# RFM96W-BB.net
KiCad netlist of a schematic drawn in EAGLE
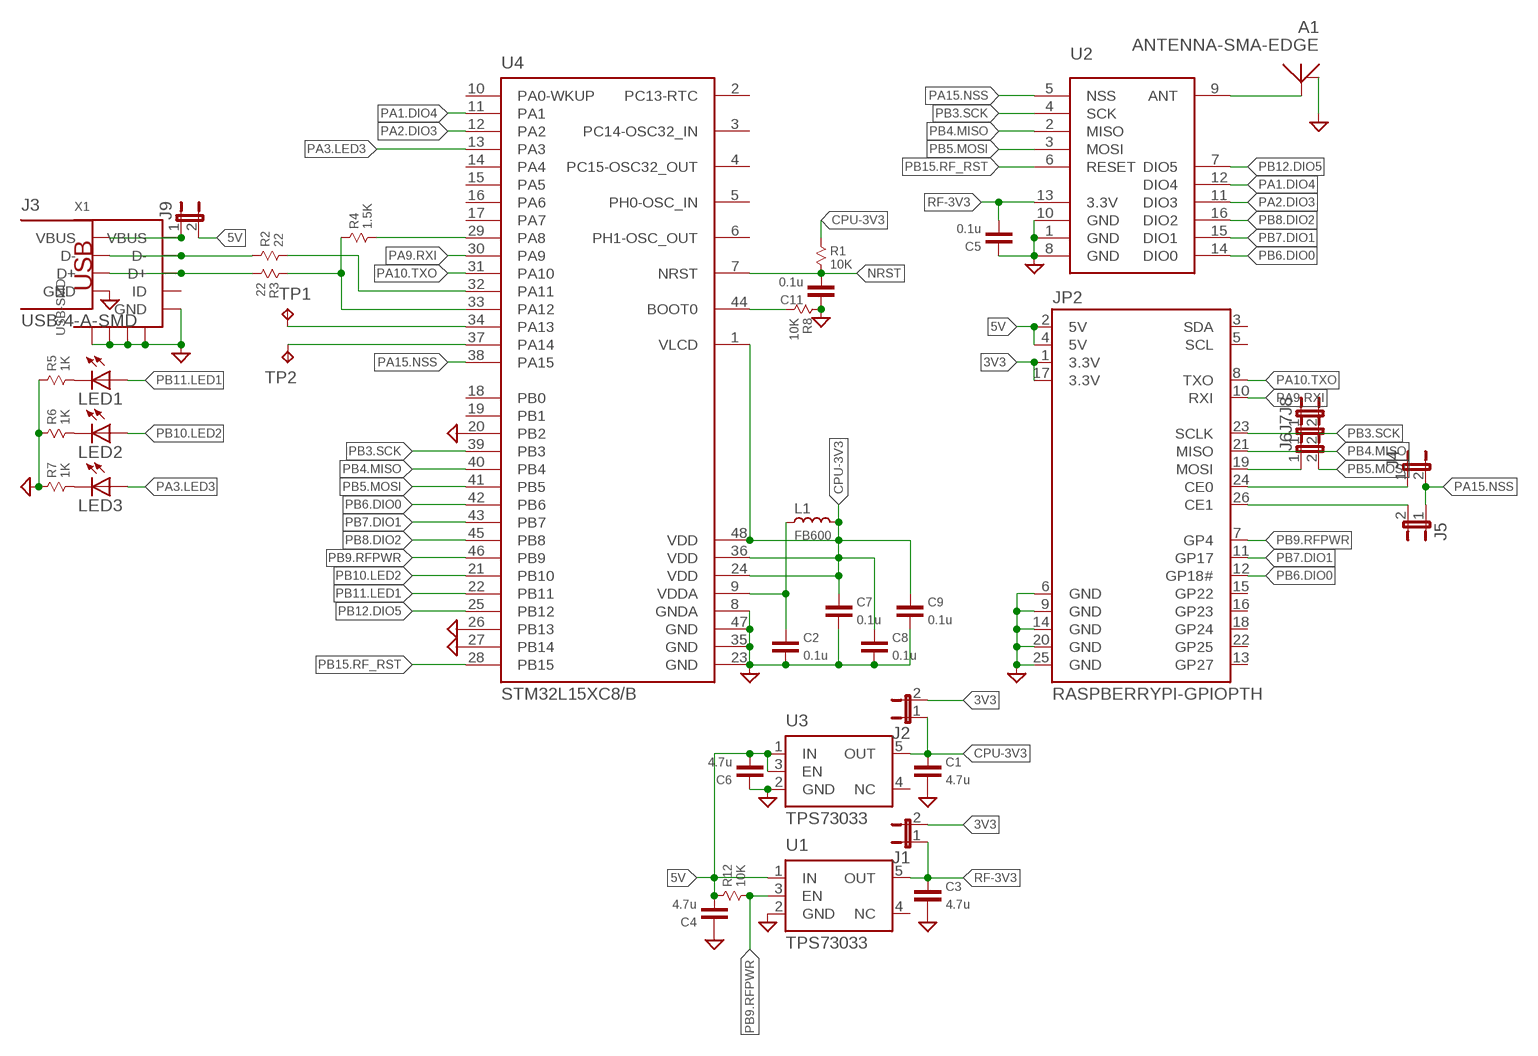
[diagram p0: schematic, sheet 1]

(export (version "E")
  (design (tool "Eeschema 10.0.6"))
  (components
    (comp (ref "A1")
      (value "ANTENNA-SMA-EDGE")
      (footprint "eagle-import:SMA-EDGE")
      (libsource (lib "eagle-import") (part "ANTENNA-SMA-EDGE"))
    )
    (comp (ref "C1")
      (value "4.7u")
      (footprint "eagle-import:0603")
      (libsource (lib "eagle-import") (part "CAP-0603"))
    )
    (comp (ref "C2")
      (value "0.1u")
      (footprint "eagle-import:0603")
      (libsource (lib "eagle-import") (part "CAP-0603"))
    )
    (comp (ref "C3")
      (value "4.7u")
      (footprint "eagle-import:0603")
      (libsource (lib "eagle-import") (part "CAP-0603"))
    )
    (comp (ref "C4")
      (value "4.7u")
      (footprint "eagle-import:0603")
      (libsource (lib "eagle-import") (part "CAP-0603"))
    )
    (comp (ref "C5")
      (value "0.1u")
      (footprint "eagle-import:0603")
      (libsource (lib "eagle-import") (part "CAP-0603"))
    )
    (comp (ref "C6")
      (value "4.7u")
      (footprint "eagle-import:0603")
      (libsource (lib "eagle-import") (part "CAP-0603"))
    )
    (comp (ref "C7")
      (value "0.1u")
      (footprint "eagle-import:0603")
      (libsource (lib "eagle-import") (part "CAP-0603"))
    )
    (comp (ref "C8")
      (value "0.1u")
      (footprint "eagle-import:0603")
      (libsource (lib "eagle-import") (part "CAP-0603"))
    )
    (comp (ref "C9")
      (value "0.1u")
      (footprint "eagle-import:0603")
      (libsource (lib "eagle-import") (part "CAP-0603"))
    )
    (comp (ref "C11")
      (value "0.1u")
      (footprint "eagle-import:0603")
      (libsource (lib "eagle-import") (part "CAP-0603"))
    )
    (comp (ref "J1")
      (value "JUMPER-2SMD-NO")
      (footprint "eagle-import:SJ_2S-NO")
      (libsource (lib "eagle-import") (part "JUMPER-2SMD-NO"))
    )
    (comp (ref "J2")
      (value "JUMPER-2SMD-NO")
      (footprint "eagle-import:SJ_2S-NO")
      (libsource (lib "eagle-import") (part "JUMPER-2SMD-NO"))
    )
    (comp (ref "J3")
      (value "USB-4-A-SMD")
      (footprint "eagle-import:USB-A-SMD")
      (libsource (lib "eagle-import") (part "USB-4-A-SMD"))
    )
    (comp (ref "J4")
      (value "JUMPER-2SMD-NO")
      (footprint "eagle-import:SJ_2S-NO")
      (libsource (lib "eagle-import") (part "JUMPER-2SMD-NO"))
    )
    (comp (ref "J5")
      (value "JUMPER-2SMD-NO")
      (footprint "eagle-import:SJ_2S-NO")
      (libsource (lib "eagle-import") (part "JUMPER-2SMD-NO"))
    )
    (comp (ref "J6")
      (value "JUMPER-2SMD-NO")
      (footprint "eagle-import:SJ_2S-NO")
      (libsource (lib "eagle-import") (part "JUMPER-2SMD-NO"))
    )
    (comp (ref "J7")
      (value "JUMPER-2SMD-NO")
      (footprint "eagle-import:SJ_2S-NO")
      (libsource (lib "eagle-import") (part "JUMPER-2SMD-NO"))
    )
    (comp (ref "J8")
      (value "JUMPER-2SMD-NO")
      (footprint "eagle-import:SJ_2S-NO")
      (libsource (lib "eagle-import") (part "JUMPER-2SMD-NO"))
    )
    (comp (ref "J9")
      (value "JUMPER-2SMD-NO")
      (footprint "eagle-import:SJ_2S-NO")
      (libsource (lib "eagle-import") (part "JUMPER-2SMD-NO"))
    )
    (comp (ref "JP2")
      (value "RASPBERRYPI-GPIOPTH")
      (footprint "eagle-import:2X13-SHROUDED")
      (libsource (lib "eagle-import") (part "RASPBERRYPI-GPIOPTH"))
    )
    (comp (ref "L1")
      (value "FB600")
      (footprint "eagle-import:0603")
      (libsource (lib "eagle-import") (part "INDUCTOR-0603"))
    )
    (comp (ref "LED1")
      (value "LEDCHIPLED_0603")
      (footprint "eagle-import:CHIPLED_0603")
      (libsource (lib "eagle-import") (part "LEDCHIPLED_0603"))
    )
    (comp (ref "LED2")
      (value "LEDCHIPLED_0603")
      (footprint "eagle-import:CHIPLED_0603")
      (libsource (lib "eagle-import") (part "LEDCHIPLED_0603"))
    )
    (comp (ref "LED3")
      (value "LEDCHIPLED_0603")
      (footprint "eagle-import:CHIPLED_0603")
      (libsource (lib "eagle-import") (part "LEDCHIPLED_0603"))
    )
    (comp (ref "R1")
      (value "10K")
      (footprint "eagle-import:0603")
      (libsource (lib "eagle-import") (part "RESISTOR-0603"))
    )
    (comp (ref "R2")
      (value "22")
      (footprint "eagle-import:0603")
      (libsource (lib "eagle-import") (part "RESISTOR-0603"))
    )
    (comp (ref "R3")
      (value "22")
      (footprint "eagle-import:0603")
      (libsource (lib "eagle-import") (part "RESISTOR-0603"))
    )
    (comp (ref "R4")
      (value "1.5K")
      (footprint "eagle-import:0603")
      (libsource (lib "eagle-import") (part "RESISTOR-0603"))
    )
    (comp (ref "R5")
      (value "1K")
      (footprint "eagle-import:0603")
      (libsource (lib "eagle-import") (part "RESISTOR-0603"))
    )
    (comp (ref "R6")
      (value "1K")
      (footprint "eagle-import:0603")
      (libsource (lib "eagle-import") (part "RESISTOR-0603"))
    )
    (comp (ref "R7")
      (value "1K")
      (footprint "eagle-import:0603")
      (libsource (lib "eagle-import") (part "RESISTOR-0603"))
    )
    (comp (ref "R8")
      (value "10K")
      (footprint "eagle-import:0603")
      (libsource (lib "eagle-import") (part "RESISTOR-0603"))
    )
    (comp (ref "R12")
      (value "10K")
      (footprint "eagle-import:0603")
      (libsource (lib "eagle-import") (part "RESISTOR-0603"))
    )
    (comp (ref "TP1")
      (value "TPTP14R")
      (footprint "eagle-import:TP14R")
      (libsource (lib "eagle-import") (part "TPTP14R"))
    )
    (comp (ref "TP2")
      (value "TPTP14R")
      (footprint "eagle-import:TP14R")
      (libsource (lib "eagle-import") (part "TPTP14R"))
    )
    (comp (ref "U1")
      (value "TPS73033")
      (footprint "eagle-import:SOT23-5")
      (libsource (lib "eagle-import") (part "TPS73033"))
    )
    (comp (ref "U2")
      (value "RFM9XW")
      (footprint "eagle-import:RFM9XW")
      (libsource (lib "eagle-import") (part "RFM9XW"))
    )
    (comp (ref "U3")
      (value "TPS73033")
      (footprint "eagle-import:SOT23-5")
      (libsource (lib "eagle-import") (part "TPS73033"))
    )
    (comp (ref "U4")
      (value "STM32L15XC8/B")
      (footprint "eagle-import:LQFP48")
      (libsource (lib "eagle-import") (part "STM32L15XC8/B"))
    )
    (comp (ref "X1")
      (value "USB-SMD")
      (footprint "eagle-import:USB-MINIB")
      (libsource (lib "eagle-import") (part "USB-SMD"))
    )
  )
  (nets
    (net (code "1") (name "3V3") (class "Default")
      (node (ref "J1") (pin "2") (pinfunction "2_2") (pintype "passive"))
      (node (ref "J2") (pin "2") (pinfunction "2_2") (pintype "passive"))
      (node (ref "JP2") (pin "1") (pinfunction "3.3V_1") (pintype "power_in"))
      (node (ref "JP2") (pin "17") (pinfunction "3.3V_17") (pintype "power_in"))
    )
    (net (code "2") (name "5V") (class "Default")
      (node (ref "C4") (pin "1") (pinfunction "1_1") (pintype "passive"))
      (node (ref "C6") (pin "1") (pinfunction "1_1") (pintype "passive"))
      (node (ref "J9") (pin "2") (pinfunction "2_2") (pintype "passive"))
      (node (ref "JP2") (pin "2") (pinfunction "5V_2") (pintype "power_in"))
      (node (ref "JP2") (pin "4") (pinfunction "5V_4") (pintype "power_in"))
      (node (ref "R12") (pin "1") (pinfunction "1_1") (pintype "passive"))
      (node (ref "U1") (pin "1") (pinfunction "IN_1") (pintype "passive"))
      (node (ref "U3") (pin "1") (pinfunction "IN_1") (pintype "passive"))
      (node (ref "U3") (pin "3") (pinfunction "EN_3") (pintype "input"))
    )
    (net (code "3") (name "CPU-3V3") (class "Default")
      (node (ref "C1") (pin "2") (pinfunction "2_2") (pintype "passive"))
      (node (ref "C7") (pin "2") (pinfunction "2_2") (pintype "passive"))
      (node (ref "C8") (pin "2") (pinfunction "2_2") (pintype "passive"))
      (node (ref "C9") (pin "2") (pinfunction "2_2") (pintype "passive"))
      (node (ref "J2") (pin "1") (pinfunction "1_1") (pintype "passive"))
      (node (ref "L1") (pin "2") (pinfunction "2_2") (pintype "passive"))
      (node (ref "R1") (pin "1") (pinfunction "1_1") (pintype "passive"))
      (node (ref "U3") (pin "5") (pinfunction "OUT_5") (pintype "passive"))
      (node (ref "U4") (pin "1") (pinfunction "VLCD_1") (pintype "passive"))
      (node (ref "U4") (pin "24") (pinfunction "VDD_24") (pintype "power_in"))
      (node (ref "U4") (pin "36") (pinfunction "VDD_36") (pintype "power_in"))
      (node (ref "U4") (pin "48") (pinfunction "VDD_48") (pintype "power_in"))
    )
    (net (code "4") (name "GND") (class "Default")
      (node (ref "A1") (pin "GND@1") (pinfunction "GND_GND@1") (pintype "power_in"))
      (node (ref "C1") (pin "1") (pinfunction "1_1") (pintype "passive"))
      (node (ref "C11") (pin "2") (pinfunction "2_2") (pintype "passive"))
      (node (ref "C2") (pin "1") (pinfunction "1_1") (pintype "passive"))
      (node (ref "C3") (pin "1") (pinfunction "1_1") (pintype "passive"))
      (node (ref "C4") (pin "2") (pinfunction "2_2") (pintype "passive"))
      (node (ref "C5") (pin "2") (pinfunction "2_2") (pintype "passive"))
      (node (ref "C6") (pin "2") (pinfunction "2_2") (pintype "passive"))
      (node (ref "C7") (pin "1") (pinfunction "1_1") (pintype "passive"))
      (node (ref "C8") (pin "1") (pinfunction "1_1") (pintype "passive"))
      (node (ref "C9") (pin "1") (pinfunction "1_1") (pintype "passive"))
      (node (ref "J3") (pin "GND") (pinfunction "GND_GND") (pintype "power_in"))
      (node (ref "JP2") (pin "14") (pinfunction "GND_14") (pintype "power_in"))
      (node (ref "JP2") (pin "20") (pinfunction "GND_20") (pintype "power_in"))
      (node (ref "JP2") (pin "25") (pinfunction "GND_25") (pintype "power_in"))
      (node (ref "JP2") (pin "6") (pinfunction "GND_6") (pintype "power_in"))
      (node (ref "JP2") (pin "9") (pinfunction "GND_9") (pintype "power_in"))
      (node (ref "R5") (pin "1") (pinfunction "1_1") (pintype "passive"))
      (node (ref "R6") (pin "1") (pinfunction "1_1") (pintype "passive"))
      (node (ref "R7") (pin "1") (pinfunction "1_1") (pintype "passive"))
      (node (ref "R8") (pin "1") (pinfunction "1_1") (pintype "passive"))
      (node (ref "U1") (pin "2") (pinfunction "GND_2") (pintype "power_in"))
      (node (ref "U2") (pin "1") (pinfunction "GND_1") (pintype "power_in"))
      (node (ref "U2") (pin "10") (pinfunction "GND_10") (pintype "power_in"))
      (node (ref "U2") (pin "8") (pinfunction "GND_8") (pintype "power_in"))
      (node (ref "U3") (pin "2") (pinfunction "GND_2") (pintype "power_in"))
      (node (ref "U4") (pin "20") (pinfunction "PB2_20") (pintype "bidirectional"))
      (node (ref "U4") (pin "23") (pinfunction "GND_23") (pintype "power_in"))
      (node (ref "U4") (pin "26") (pinfunction "PB13_26") (pintype "bidirectional"))
      (node (ref "U4") (pin "27") (pinfunction "PB14_27") (pintype "bidirectional"))
      (node (ref "U4") (pin "35") (pinfunction "GND_35") (pintype "power_in"))
      (node (ref "U4") (pin "47") (pinfunction "GND_47") (pintype "power_in"))
      (node (ref "U4") (pin "8") (pinfunction "GNDA_8") (pintype "power_in"))
      (node (ref "X1") (pin "GND") (pinfunction "GND_GND") (pintype "power_in"))
      (node (ref "X1") (pin "GND@1") (pinfunction "GND_GND@1") (pintype "power_in"))
      (node (ref "X1") (pin "GND@2") (pinfunction "GND_GND@2") (pintype "power_in"))
      (node (ref "X1") (pin "GND@3") (pinfunction "GND_GND@3") (pintype "power_in"))
      (node (ref "X1") (pin "GND@4") (pinfunction "GND_GND@4") (pintype "power_in"))
    )
    (net (code "5") (name "NRST") (class "Default")
      (node (ref "C11") (pin "1") (pinfunction "1_1") (pintype "passive"))
      (node (ref "R1") (pin "2") (pinfunction "2_2") (pintype "passive"))
      (node (ref "U4") (pin "7") (pinfunction "NRST_7") (pintype "input"))
    )
    (net (code "6") (name "Net-(J3-PadD+)") (class "Default")
      (node (ref "J3") (pin "D+") (pinfunction "D+_D+") (pintype "bidirectional"))
      (node (ref "R3") (pin "2") (pinfunction "2_2") (pintype "passive"))
      (node (ref "X1") (pin "D+") (pinfunction "D+_D+") (pintype "bidirectional"))
    )
    (net (code "7") (name "Net-(J3-PadD-)") (class "Default")
      (node (ref "J3") (pin "D-") (pinfunction "D-_D-") (pintype "bidirectional"))
      (node (ref "R2") (pin "1") (pinfunction "1_1") (pintype "passive"))
      (node (ref "X1") (pin "D-") (pinfunction "D-_D-") (pintype "bidirectional"))
    )
    (net (code "8") (name "Net-(J3-VBUS)") (class "Default")
      (node (ref "J3") (pin "VUSB") (pinfunction "VBUS_VUSB") (pintype "passive"))
      (node (ref "J9") (pin "1") (pinfunction "1_1") (pintype "passive"))
      (node (ref "X1") (pin "VBUS") (pinfunction "VBUS_VBUS") (pintype "passive"))
    )
    (net (code "9") (name "Net-(JP2-CE0)") (class "Default")
      (node (ref "J4") (pin "1") (pinfunction "1_1") (pintype "passive"))
      (node (ref "JP2") (pin "24") (pinfunction "CE0_24") (pintype "output"))
    )
    (net (code "10") (name "Net-(JP2-CE1)") (class "Default")
      (node (ref "J5") (pin "2") (pinfunction "2_2") (pintype "passive"))
      (node (ref "JP2") (pin "26") (pinfunction "CE1_26") (pintype "output"))
    )
    (net (code "11") (name "Net-(JP2-MISO)") (class "Default")
      (node (ref "J7") (pin "1") (pinfunction "1_1") (pintype "passive"))
      (node (ref "JP2") (pin "21") (pinfunction "MISO_21") (pintype "input"))
    )
    (net (code "12") (name "Net-(JP2-MOSI)") (class "Default")
      (node (ref "J6") (pin "1") (pinfunction "1_1") (pintype "passive"))
      (node (ref "JP2") (pin "19") (pinfunction "MOSI_19") (pintype "output"))
    )
    (net (code "13") (name "Net-(JP2-SCLK)") (class "Default")
      (node (ref "J8") (pin "1") (pinfunction "1_1") (pintype "passive"))
      (node (ref "JP2") (pin "23") (pinfunction "SCLK_23") (pintype "output"))
    )
    (net (code "14") (name "Net-(LED1-PadC)") (class "Default")
      (node (ref "LED1") (pin "C") (pinfunction "C_C") (pintype "passive"))
      (node (ref "R5") (pin "2") (pinfunction "2_2") (pintype "passive"))
    )
    (net (code "15") (name "Net-(LED2-PadC)") (class "Default")
      (node (ref "LED2") (pin "C") (pinfunction "C_C") (pintype "passive"))
      (node (ref "R6") (pin "2") (pinfunction "2_2") (pintype "passive"))
    )
    (net (code "16") (name "Net-(LED3-PadC)") (class "Default")
      (node (ref "LED3") (pin "C") (pinfunction "C_C") (pintype "passive"))
      (node (ref "R7") (pin "2") (pinfunction "2_2") (pintype "passive"))
    )
    (net (code "17") (name "Net-(U2-ANT)") (class "Default")
      (node (ref "A1") (pin "ANT") (pinfunction "ANT_ANT") (pintype "passive"))
      (node (ref "U2") (pin "9") (pinfunction "ANT_9") (pintype "passive"))
    )
    (net (code "18") (name "Net-(U4-BOOT0)") (class "Default")
      (node (ref "R8") (pin "2") (pinfunction "2_2") (pintype "passive"))
      (node (ref "U4") (pin "44") (pinfunction "BOOT0_44") (pintype "input"))
    )
    (net (code "19") (name "Net-(U4-PA8)") (class "Default")
      (node (ref "R4") (pin "2") (pinfunction "2_2") (pintype "passive"))
      (node (ref "U4") (pin "29") (pinfunction "PA8_29") (pintype "bidirectional"))
    )
    (net (code "20") (name "Net-(U4-PA11)") (class "Default")
      (node (ref "R2") (pin "2") (pinfunction "2_2") (pintype "passive"))
      (node (ref "U4") (pin "32") (pinfunction "PA11_32") (pintype "bidirectional"))
    )
    (net (code "21") (name "Net-(U4-PA12)") (class "Default")
      (node (ref "R3") (pin "1") (pinfunction "1_1") (pintype "passive"))
      (node (ref "R4") (pin "1") (pinfunction "1_1") (pintype "passive"))
      (node (ref "U4") (pin "33") (pinfunction "PA12_33") (pintype "bidirectional"))
    )
    (net (code "22") (name "Net-(U4-PA13)") (class "Default")
      (node (ref "TP1") (pin "TP") (pinfunction "TP_TP") (pintype "input"))
      (node (ref "U4") (pin "34") (pinfunction "PA13_34") (pintype "bidirectional"))
    )
    (net (code "23") (name "Net-(U4-PA14)") (class "Default")
      (node (ref "TP2") (pin "TP") (pinfunction "TP_TP") (pintype "input"))
      (node (ref "U4") (pin "37") (pinfunction "PA14_37") (pintype "bidirectional"))
    )
    (net (code "24") (name "Net-(U4-VDDA)") (class "Default")
      (node (ref "C2") (pin "2") (pinfunction "2_2") (pintype "passive"))
      (node (ref "L1") (pin "1") (pinfunction "1_1") (pintype "passive"))
      (node (ref "U4") (pin "9") (pinfunction "VDDA_9") (pintype "power_in"))
    )
    (net (code "25") (name "PA1.DIO4") (class "Default")
      (node (ref "U2") (pin "12") (pinfunction "DIO4_12") (pintype "bidirectional"))
      (node (ref "U4") (pin "11") (pinfunction "PA1_11") (pintype "bidirectional"))
    )
    (net (code "26") (name "PA2.DIO3") (class "Default")
      (node (ref "U2") (pin "11") (pinfunction "DIO3_11") (pintype "bidirectional"))
      (node (ref "U4") (pin "12") (pinfunction "PA2_12") (pintype "bidirectional"))
    )
    (net (code "27") (name "PA3.LED3") (class "Default")
      (node (ref "LED3") (pin "A") (pinfunction "A_A") (pintype "passive"))
      (node (ref "U4") (pin "13") (pinfunction "PA3_13") (pintype "bidirectional"))
    )
    (net (code "28") (name "PA9.RXI") (class "Default")
      (node (ref "JP2") (pin "10") (pinfunction "RXI_10") (pintype "input"))
      (node (ref "U4") (pin "30") (pinfunction "PA9_30") (pintype "bidirectional"))
    )
    (net (code "29") (name "PA10.TXO") (class "Default")
      (node (ref "JP2") (pin "8") (pinfunction "TXO_8") (pintype "output"))
      (node (ref "U4") (pin "31") (pinfunction "PA10_31") (pintype "bidirectional"))
    )
    (net (code "30") (name "PA15.NSS") (class "Default")
      (node (ref "J4") (pin "2") (pinfunction "2_2") (pintype "passive"))
      (node (ref "J5") (pin "1") (pinfunction "1_1") (pintype "passive"))
      (node (ref "U2") (pin "5") (pinfunction "NSS_5") (pintype "input"))
      (node (ref "U4") (pin "38") (pinfunction "PA15_38") (pintype "bidirectional"))
    )
    (net (code "31") (name "PB3.SCK") (class "Default")
      (node (ref "J8") (pin "2") (pinfunction "2_2") (pintype "passive"))
      (node (ref "U2") (pin "4") (pinfunction "SCK_4") (pintype "input"))
      (node (ref "U4") (pin "39") (pinfunction "PB3_39") (pintype "bidirectional"))
    )
    (net (code "32") (name "PB4.MISO") (class "Default")
      (node (ref "J7") (pin "2") (pinfunction "2_2") (pintype "passive"))
      (node (ref "U2") (pin "2") (pinfunction "MISO_2") (pintype "output"))
      (node (ref "U4") (pin "40") (pinfunction "PB4_40") (pintype "bidirectional"))
    )
    (net (code "33") (name "PB5.MOSI") (class "Default")
      (node (ref "J6") (pin "2") (pinfunction "2_2") (pintype "passive"))
      (node (ref "U2") (pin "3") (pinfunction "MOSI_3") (pintype "input"))
      (node (ref "U4") (pin "41") (pinfunction "PB5_41") (pintype "bidirectional"))
    )
    (net (code "34") (name "PB6.DIO0") (class "Default")
      (node (ref "JP2") (pin "12") (pinfunction "GP18#_12") (pintype "bidirectional"))
      (node (ref "U2") (pin "14") (pinfunction "DIO0_14") (pintype "bidirectional"))
      (node (ref "U4") (pin "42") (pinfunction "PB6_42") (pintype "bidirectional"))
    )
    (net (code "35") (name "PB7.DIO1") (class "Default")
      (node (ref "JP2") (pin "11") (pinfunction "GP17_11") (pintype "bidirectional"))
      (node (ref "U2") (pin "15") (pinfunction "DIO1_15") (pintype "bidirectional"))
      (node (ref "U4") (pin "43") (pinfunction "PB7_43") (pintype "bidirectional"))
    )
    (net (code "36") (name "PB8.DIO2") (class "Default")
      (node (ref "U2") (pin "16") (pinfunction "DIO2_16") (pintype "bidirectional"))
      (node (ref "U4") (pin "45") (pinfunction "PB8_45") (pintype "bidirectional"))
    )
    (net (code "37") (name "PB9.RFPWR") (class "Default")
      (node (ref "JP2") (pin "7") (pinfunction "GP4_7") (pintype "bidirectional"))
      (node (ref "R12") (pin "2") (pinfunction "2_2") (pintype "passive"))
      (node (ref "U1") (pin "3") (pinfunction "EN_3") (pintype "input"))
      (node (ref "U4") (pin "46") (pinfunction "PB9_46") (pintype "bidirectional"))
    )
    (net (code "38") (name "PB10.LED2") (class "Default")
      (node (ref "LED2") (pin "A") (pinfunction "A_A") (pintype "passive"))
      (node (ref "U4") (pin "21") (pinfunction "PB10_21") (pintype "bidirectional"))
    )
    (net (code "39") (name "PB11.LED1") (class "Default")
      (node (ref "LED1") (pin "A") (pinfunction "A_A") (pintype "passive"))
      (node (ref "U4") (pin "22") (pinfunction "PB11_22") (pintype "bidirectional"))
    )
    (net (code "40") (name "PB12.DIO5") (class "Default")
      (node (ref "U2") (pin "7") (pinfunction "DIO5_7") (pintype "bidirectional"))
      (node (ref "U4") (pin "25") (pinfunction "PB12_25") (pintype "bidirectional"))
    )
    (net (code "41") (name "PB15.RF_RST") (class "Default")
      (node (ref "U2") (pin "6") (pinfunction "RESET_6") (pintype "input"))
      (node (ref "U4") (pin "28") (pinfunction "PB15_28") (pintype "bidirectional"))
    )
    (net (code "42") (name "RF-3V3") (class "Default")
      (node (ref "C3") (pin "2") (pinfunction "2_2") (pintype "passive"))
      (node (ref "C5") (pin "1") (pinfunction "1_1") (pintype "passive"))
      (node (ref "J1") (pin "1") (pinfunction "1_1") (pintype "passive"))
      (node (ref "U1") (pin "5") (pinfunction "OUT_5") (pintype "passive"))
      (node (ref "U2") (pin "13") (pinfunction "3.3V_13") (pintype "power_in"))
    )
    (net (code "43") (name "unconnected-(JP2-GP22-Pad15)") (class "Default")
      (node (ref "JP2") (pin "15") (pinfunction "GP22_15") (pintype "bidirectional"))
    )
    (net (code "44") (name "unconnected-(JP2-GP23-Pad16)") (class "Default")
      (node (ref "JP2") (pin "16") (pinfunction "GP23_16") (pintype "bidirectional"))
    )
    (net (code "45") (name "unconnected-(JP2-GP24-Pad18)") (class "Default")
      (node (ref "JP2") (pin "18") (pinfunction "GP24_18") (pintype "bidirectional"))
    )
    (net (code "46") (name "unconnected-(JP2-GP25-Pad22)") (class "Default")
      (node (ref "JP2") (pin "22") (pinfunction "GP25_22") (pintype "bidirectional"))
    )
    (net (code "47") (name "unconnected-(JP2-GP27-Pad13)") (class "Default")
      (node (ref "JP2") (pin "13") (pinfunction "GP27_13") (pintype "bidirectional"))
    )
    (net (code "48") (name "unconnected-(JP2-SCL-Pad5)") (class "Default")
      (node (ref "JP2") (pin "5") (pinfunction "SCL_5") (pintype "bidirectional"))
    )
    (net (code "49") (name "unconnected-(JP2-SDA-Pad3)") (class "Default")
      (node (ref "JP2") (pin "3") (pinfunction "SDA_3") (pintype "bidirectional"))
    )
    (net (code "50") (name "unconnected-(U1-NC-Pad4)") (class "Default")
      (node (ref "U1") (pin "4") (pinfunction "NC_4") (pintype "no_connect"))
    )
    (net (code "51") (name "unconnected-(U3-NC-Pad4)") (class "Default")
      (node (ref "U3") (pin "4") (pinfunction "NC_4") (pintype "no_connect"))
    )
    (net (code "52") (name "unconnected-(U4-PA0-WKUP-Pad10)") (class "Default")
      (node (ref "U4") (pin "10") (pinfunction "PA0-WKUP_10") (pintype "bidirectional"))
    )
    (net (code "53") (name "unconnected-(U4-PA4-Pad14)") (class "Default")
      (node (ref "U4") (pin "14") (pinfunction "PA4_14") (pintype "bidirectional"))
    )
    (net (code "54") (name "unconnected-(U4-PA5-Pad15)") (class "Default")
      (node (ref "U4") (pin "15") (pinfunction "PA5_15") (pintype "bidirectional"))
    )
    (net (code "55") (name "unconnected-(U4-PA6-Pad16)") (class "Default")
      (node (ref "U4") (pin "16") (pinfunction "PA6_16") (pintype "bidirectional"))
    )
    (net (code "56") (name "unconnected-(U4-PA7-Pad17)") (class "Default")
      (node (ref "U4") (pin "17") (pinfunction "PA7_17") (pintype "bidirectional"))
    )
    (net (code "57") (name "unconnected-(U4-PB0-Pad18)") (class "Default")
      (node (ref "U4") (pin "18") (pinfunction "PB0_18") (pintype "bidirectional"))
    )
    (net (code "58") (name "unconnected-(U4-PB1-Pad19)") (class "Default")
      (node (ref "U4") (pin "19") (pinfunction "PB1_19") (pintype "bidirectional"))
    )
    (net (code "59") (name "unconnected-(U4-PC13-RTC-Pad2)") (class "Default")
      (node (ref "U4") (pin "2") (pinfunction "PC13-RTC_2") (pintype "bidirectional"))
    )
    (net (code "60") (name "unconnected-(U4-PC14-OSC32_IN-Pad3)") (class "Default")
      (node (ref "U4") (pin "3") (pinfunction "PC14-OSC32_IN_3") (pintype "bidirectional"))
    )
    (net (code "61") (name "unconnected-(U4-PC15-OSC32_OUT-Pad4)") (class "Default")
      (node (ref "U4") (pin "4") (pinfunction "PC15-OSC32_OUT_4") (pintype "bidirectional"))
    )
    (net (code "62") (name "unconnected-(U4-PH0-OSC_IN-Pad5)") (class "Default")
      (node (ref "U4") (pin "5") (pinfunction "PH0-OSC_IN_5") (pintype "bidirectional"))
    )
    (net (code "63") (name "unconnected-(U4-PH1-OSC_OUT-Pad6)") (class "Default")
      (node (ref "U4") (pin "6") (pinfunction "PH1-OSC_OUT_6") (pintype "bidirectional"))
    )
    (net (code "64") (name "unconnected-(X1-PadID)") (class "Default")
      (node (ref "X1") (pin "ID") (pinfunction "ID_ID") (pintype "bidirectional"))
    )
  )
)
